# hamtonio.net
KiCad netlist of a schematic drawn in EAGLE
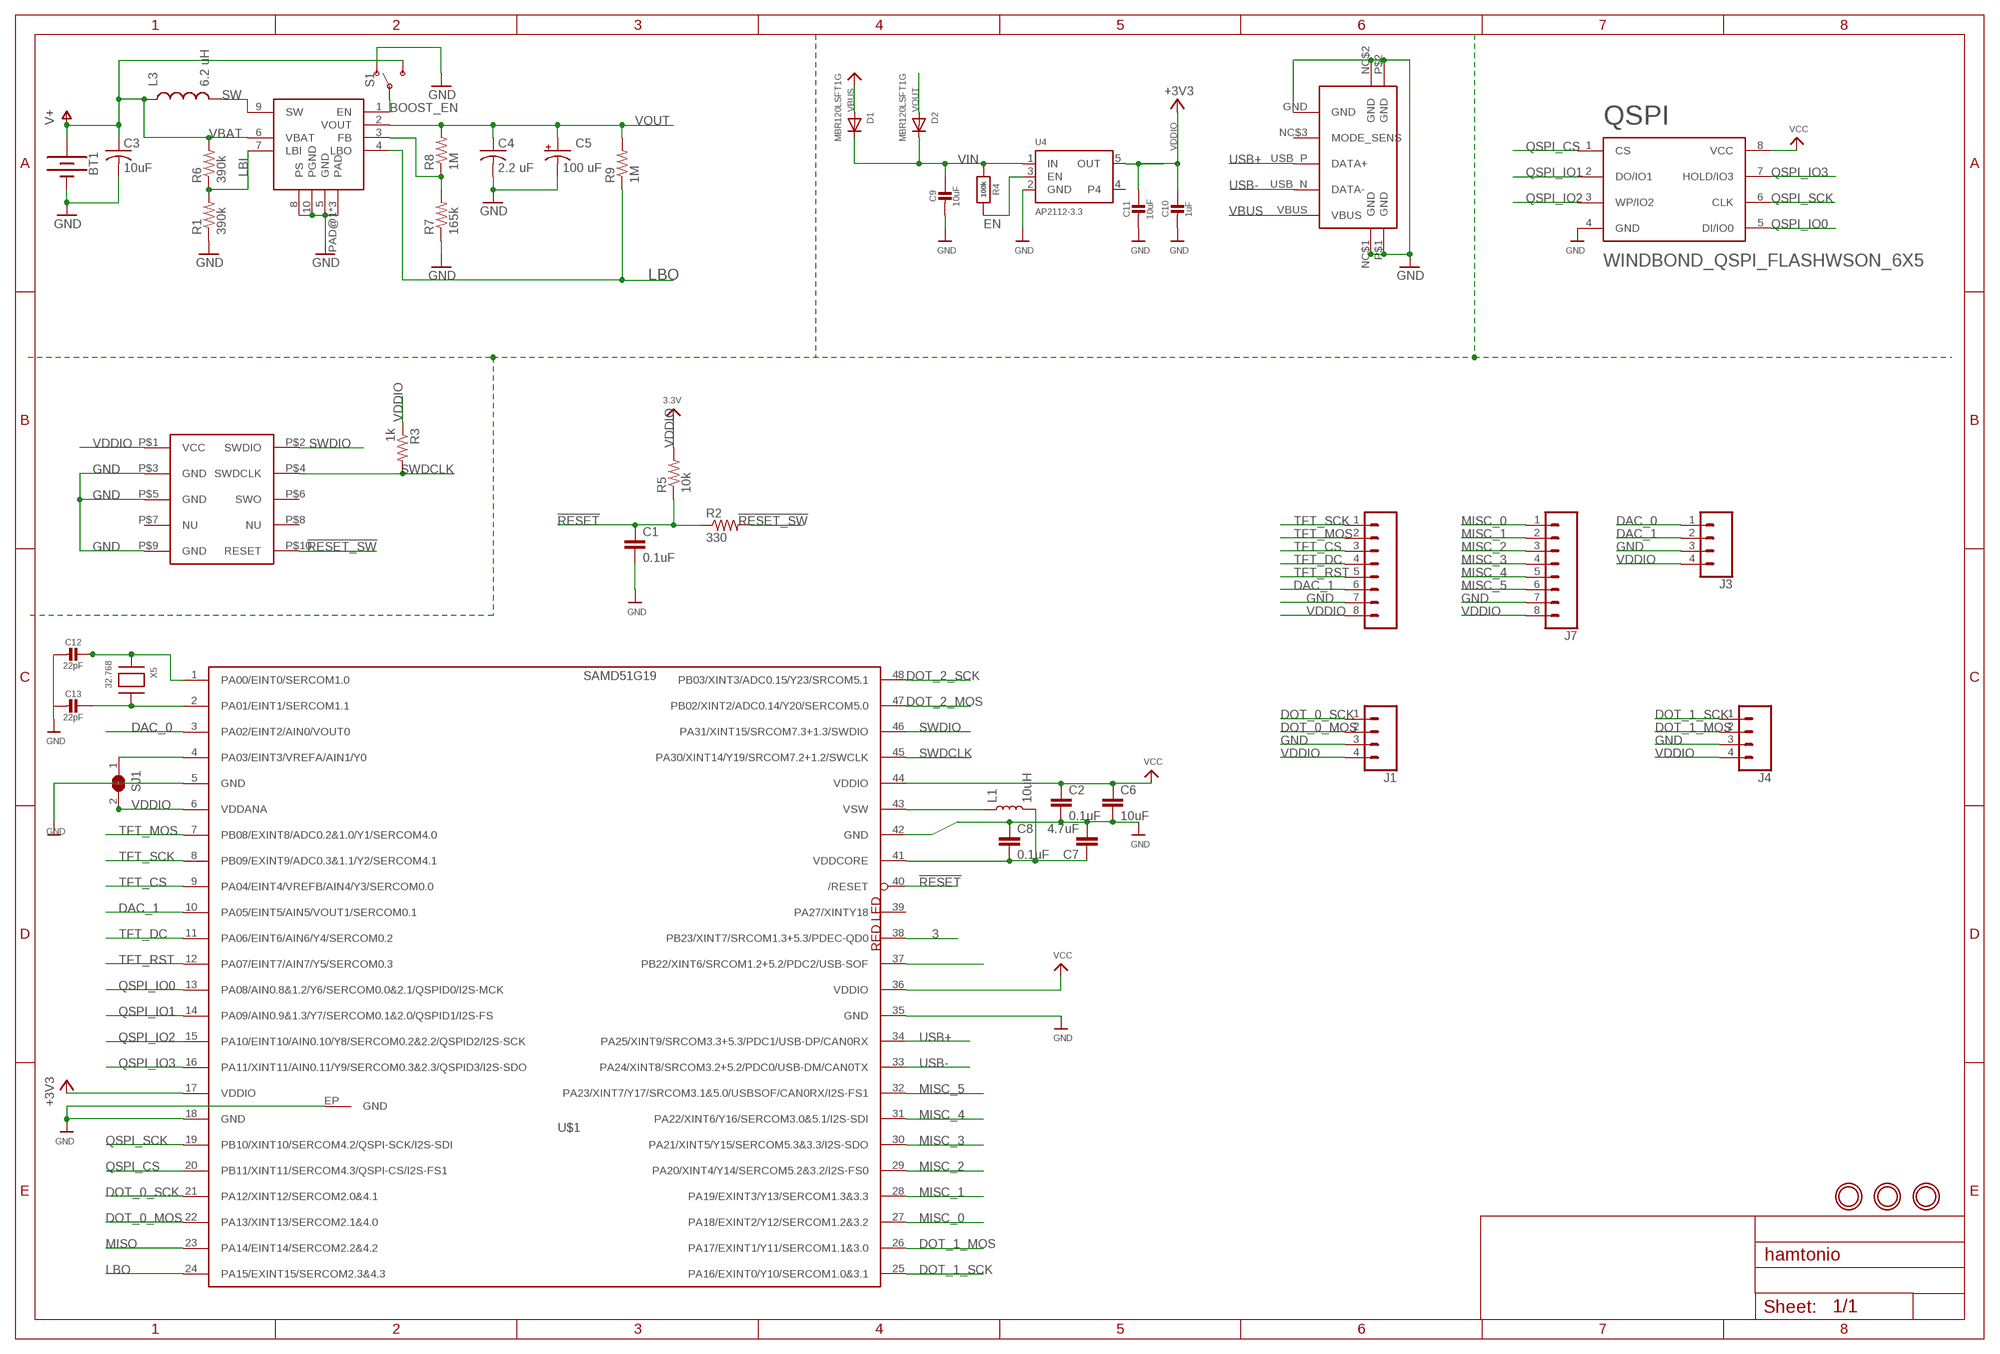
[diagram p0: schematic, sheet 1]

(export (version "E")
  (design (tool "Eeschema 10.0.6"))
  (components
    (comp (ref "BT1")
      (value "BATTERYDUAL_AA_XX")
      (footprint "eagle-import:DUAL_AA")
      (libsource (lib "eagle-import") (part "BATTERYDUAL_AA_XX"))
    )
    (comp (ref "C1")
      (value "0.1uF")
      (footprint "eagle-import:0603")
      (libsource (lib "eagle-import") (part "0.1UF-0603-25V-(+80/-20%)"))
    )
    (comp (ref "C2")
      (value "0.1uF")
      (footprint "eagle-import:0603")
      (libsource (lib "eagle-import") (part "0.1UF-0603-25V-(+80/-20%)"))
    )
    (comp (ref "C3")
      (value "10uF")
      (footprint "eagle-import:C0805K")
      (libsource (lib "eagle-import") (part "C-USC0805K"))
    )
    (comp (ref "C4")
      (value "2.2 uF")
      (footprint "eagle-import:C0805K")
      (libsource (lib "eagle-import") (part "C-USC0805K"))
    )
    (comp (ref "C5")
      (value "100 uF")
      (footprint "eagle-import:CT6032")
      (libsource (lib "eagle-import") (part "CPOL-USCT6032"))
    )
    (comp (ref "C6")
      (value "10uF")
      (footprint "eagle-import:0805")
      (libsource (lib "eagle-import") (part "10UF-0805-10V-10%"))
    )
    (comp (ref "C7")
      (value "4.7uF")
      (footprint "eagle-import:0603")
      (libsource (lib "eagle-import") (part "4.7UF0603"))
    )
    (comp (ref "C8")
      (value "0.1uF")
      (footprint "eagle-import:0603")
      (libsource (lib "eagle-import") (part "0.1UF-0603-25V-(+80/-20%)"))
    )
    (comp (ref "C9")
      (value "10uF")
      (footprint "eagle-import:0805-NO")
      (libsource (lib "eagle-import") (part "CAP_CERAMIC0805-NOOUTLINE"))
    )
    (comp (ref "C10")
      (value "1uF")
      (footprint "eagle-import:0603-NO")
      (libsource (lib "eagle-import") (part "CAP_CERAMIC0603_NO"))
    )
    (comp (ref "C11")
      (value "10uF")
      (footprint "eagle-import:0805-NO")
      (libsource (lib "eagle-import") (part "CAP_CERAMIC0805-NOOUTLINE"))
    )
    (comp (ref "C12")
      (value "22pF")
      (footprint "eagle-import:0603-NO")
      (libsource (lib "eagle-import") (part "CAP_CERAMIC0603_NO"))
    )
    (comp (ref "C13")
      (value "22pF")
      (footprint "eagle-import:0603-NO")
      (libsource (lib "eagle-import") (part "CAP_CERAMIC0603_NO"))
    )
    (comp (ref "D1")
      (value "MBR120LSFT1G")
      (footprint "eagle-import:SOD-123")
      (libsource (lib "eagle-import") (part "DIODESOD-123"))
    )
    (comp (ref "D2")
      (value "MBR120LSFT1G")
      (footprint "eagle-import:SOD-123")
      (libsource (lib "eagle-import") (part "DIODESOD-123"))
    )
    (comp (ref "J1")
      (value "CONN_041X04_NO_SILK")
      (footprint "eagle-import:1X04_NO_SILK")
      (libsource (lib "eagle-import") (part "CONN_041X04_NO_SILK"))
    )
    (comp (ref "J3")
      (value "CONN_041X04_NO_SILK")
      (footprint "eagle-import:1X04_NO_SILK")
      (libsource (lib "eagle-import") (part "CONN_041X04_NO_SILK"))
    )
    (comp (ref "J4")
      (value "CONN_041X04_NO_SILK")
      (footprint "eagle-import:1X04_NO_SILK")
      (libsource (lib "eagle-import") (part "CONN_041X04_NO_SILK"))
    )
    (comp (ref "J6")
      (value "CONN_08NO_SILK_FEMALE_PTH")
      (footprint "eagle-import:1X08_NO_SILK")
      (libsource (lib "eagle-import") (part "CONN_08NO_SILK_FEMALE_PTH"))
    )
    (comp (ref "J7")
      (value "CONN_08NO_SILK_FEMALE_PTH")
      (footprint "eagle-import:1X08_NO_SILK")
      (libsource (lib "eagle-import") (part "CONN_08NO_SILK_FEMALE_PTH"))
    )
    (comp (ref "L1")
      (value "10uH")
      (footprint "eagle-import:1007_INDUCTOR")
      (libsource (lib "eagle-import") (part "1007_INDUCTOR"))
    )
    (comp (ref "L3")
      (value "6.2 uH")
      (footprint "eagle-import:CDRH52D")
      (libsource (lib "eagle-import") (part "INDUCTORSRU1038"))
    )
    (comp (ref "QSPI")
      (value "WINDBOND_QSPI_FLASHWSON_6X5")
      (footprint "eagle-import:WSON_6X5MM")
      (libsource (lib "eagle-import") (part "WINDBOND_QSPI_FLASHWSON_6X5"))
    )
    (comp (ref "R1")
      (value "390k")
      (footprint "eagle-import:R0603")
      (libsource (lib "eagle-import") (part "R-US_R0603"))
    )
    (comp (ref "R2")
      (value "330")
      (footprint "eagle-import:R0603")
      (libsource (lib "eagle-import") (part "R-US_R0603"))
    )
    (comp (ref "R3")
      (value "1k")
      (footprint "eagle-import:R0603")
      (libsource (lib "eagle-import") (part "R-US_R0603"))
    )
    (comp (ref "R4")
      (value "100k")
      (footprint "eagle-import:0603-NO")
      (libsource (lib "eagle-import") (part "RESISTOR_0603_NOOUT"))
    )
    (comp (ref "R5")
      (value "10k")
      (footprint "eagle-import:R0603")
      (libsource (lib "eagle-import") (part "R-US_R0603"))
    )
    (comp (ref "R6")
      (value "390k")
      (footprint "eagle-import:R0603")
      (libsource (lib "eagle-import") (part "R-US_R0603"))
    )
    (comp (ref "R7")
      (value "165k")
      (footprint "eagle-import:R0603")
      (libsource (lib "eagle-import") (part "R-US_R0603"))
    )
    (comp (ref "R8")
      (value "1M")
      (footprint "eagle-import:R0603")
      (libsource (lib "eagle-import") (part "R-US_R0603"))
    )
    (comp (ref "R9")
      (value "1M")
      (footprint "eagle-import:R0603")
      (libsource (lib "eagle-import") (part "R-US_R0603"))
    )
    (comp (ref "S1")
      (value "SWITCH-SPDTSMD_C&K_JS")
      (footprint "eagle-import:SPDT_SMD")
      (libsource (lib "eagle-import") (part "SWITCH-SPDTSMD_C&K_JS"))
    )
    (comp (ref "SJ1")
      (value "SOLDERJUMPERCLOSED")
      (footprint "eagle-import:SOLDERJUMPER_CLOSEDWIRE")
      (libsource (lib "eagle-import") (part "SOLDERJUMPERCLOSED"))
    )
    (comp (ref "U$1")
      (value "SAMD51G19")
      (footprint "eagle-import:QFN-48")
      (libsource (lib "eagle-import") (part "SAMD51G"))
    )
    (comp (ref "U$2")
      (value "SWD_HEADER")
      (footprint "eagle-import:AMPHENOL_SWD")
      (libsource (lib "eagle-import") (part "SWD_HEADER"))
    )
    (comp (ref "U$8")
      (value "TPS61029")
      (footprint "eagle-import:TPS61029")
      (libsource (lib "eagle-import") (part "TPS61029"))
    )
    (comp (ref "U$12")
      (value "AMPHENOL_MICRO_USBAMPHENOL_MICRO_USB_BETTER")
      (footprint "eagle-import:BETTER_AMP_MICRO_USB")
      (libsource (lib "eagle-import") (part "AMPHENOL_MICRO_USBAMPHENOL_MICRO_USB_BETTER"))
    )
    (comp (ref "U$22")
      (value "MOUNTINGHOLE2.5")
      (footprint "eagle-import:MOUNTINGHOLE_2.5_PLATED")
      (libsource (lib "eagle-import") (part "MOUNTINGHOLE2.5"))
    )
    (comp (ref "U$34")
      (value "MOUNTINGHOLE2.5")
      (footprint "eagle-import:MOUNTINGHOLE_2.5_PLATED")
      (libsource (lib "eagle-import") (part "MOUNTINGHOLE2.5"))
    )
    (comp (ref "U$39")
      (value "MOUNTINGHOLE2.5")
      (footprint "eagle-import:MOUNTINGHOLE_2.5_PLATED")
      (libsource (lib "eagle-import") (part "MOUNTINGHOLE2.5"))
    )
    (comp (ref "U4")
      (value "AP2112-3.3")
      (footprint "eagle-import:SOT23-5")
      (libsource (lib "eagle-import") (part "VREG_SOT23-5"))
    )
    (comp (ref "X5")
      (value "32.768")
      (footprint "eagle-import:XTAL3215")
      (libsource (lib "eagle-import") (part "XTAL-3.2X1.5"))
    )
  )
  (nets
    (net (code "1") (name "+3V3") (class "Default")
      (node (ref "C10") (pin "1") (pinfunction "1_1") (pintype "passive"))
      (node (ref "C11") (pin "1") (pinfunction "1_1") (pintype "passive"))
      (node (ref "C2") (pin "1") (pinfunction "1_1") (pintype "passive"))
      (node (ref "C6") (pin "1") (pinfunction "1_1") (pintype "passive"))
      (node (ref "J1") (pin "4") (pinfunction "4_4") (pintype "passive"))
      (node (ref "J3") (pin "4") (pinfunction "4_4") (pintype "passive"))
      (node (ref "J4") (pin "4") (pinfunction "4_4") (pintype "passive"))
      (node (ref "J6") (pin "8") (pinfunction "8_8") (pintype "passive"))
      (node (ref "J7") (pin "8") (pinfunction "8_8") (pintype "passive"))
      (node (ref "QSPI") (pin "8") (pinfunction "VCC_8") (pintype "passive"))
      (node (ref "R3") (pin "1") (pinfunction "1_1") (pintype "passive"))
      (node (ref "R5") (pin "2") (pinfunction "2_2") (pintype "passive"))
      (node (ref "SJ1") (pin "2") (pinfunction "2_2") (pintype "passive"))
      (node (ref "U$1") (pin "17") (pinfunction "VDDIO_17") (pintype "power_in"))
      (node (ref "U$1") (pin "36") (pinfunction "VDDIO_36") (pintype "bidirectional"))
      (node (ref "U$1") (pin "44") (pinfunction "VDDIO_44") (pintype "bidirectional"))
      (node (ref "U$1") (pin "6") (pinfunction "VDDANA_6") (pintype "power_in"))
      (node (ref "U$2") (pin "P$1") (pinfunction "VCC_P$1") (pintype "bidirectional"))
      (node (ref "U4") (pin "5") (pinfunction "OUT_5") (pintype "power_in"))
    )
    (net (code "2") (name "/3") (class "Default")
      (node (ref "U$1") (pin "38") (pinfunction "PB23/XINT7/SRCOM1.3+5.3/PDEC-QD0_38") (pintype "bidirectional"))
    )
    (net (code "3") (name "/BOOST_EN") (class "Default")
      (node (ref "S1") (pin "P$2") (pinfunction "P_P$2") (pintype "passive"))
      (node (ref "S1") (pin "P$5") (pinfunction "P_P$5") (pintype "passive"))
      (node (ref "U$8") (pin "1") (pinfunction "EN_1") (pintype "bidirectional"))
    )
    (net (code "4") (name "/DAC_0") (class "Default")
      (node (ref "J3") (pin "1") (pinfunction "1_1") (pintype "passive"))
      (node (ref "U$1") (pin "3") (pinfunction "PA02/EINT2/AIN0/VOUT0_3") (pintype "bidirectional"))
    )
    (net (code "5") (name "/DAC_1") (class "Default")
      (node (ref "J3") (pin "2") (pinfunction "2_2") (pintype "passive"))
      (node (ref "J6") (pin "6") (pinfunction "6_6") (pintype "passive"))
      (node (ref "U$1") (pin "10") (pinfunction "PA05/EINT5/AIN5/VOUT1/SERCOM0.1_10") (pintype "bidirectional"))
    )
    (net (code "6") (name "/DOT_0_MOS") (class "Default")
      (node (ref "J1") (pin "2") (pinfunction "2_2") (pintype "passive"))
      (node (ref "U$1") (pin "22") (pinfunction "PA13/XINT13/SERCOM2.1&4.0_22") (pintype "bidirectional"))
    )
    (net (code "7") (name "/DOT_0_SCK") (class "Default")
      (node (ref "J1") (pin "1") (pinfunction "1_1") (pintype "passive"))
      (node (ref "U$1") (pin "21") (pinfunction "PA12/XINT12/SERCOM2.0&4.1_21") (pintype "bidirectional"))
    )
    (net (code "8") (name "/DOT_1_MOS") (class "Default")
      (node (ref "J4") (pin "2") (pinfunction "2_2") (pintype "passive"))
      (node (ref "U$1") (pin "26") (pinfunction "PA17/EXINT1/Y11/SERCOM1.1&3.0_26") (pintype "bidirectional"))
    )
    (net (code "9") (name "/DOT_1_SCK") (class "Default")
      (node (ref "J4") (pin "1") (pinfunction "1_1") (pintype "passive"))
      (node (ref "U$1") (pin "25") (pinfunction "PA16/EXINT0/Y10/SERCOM1.0&3.1_25") (pintype "bidirectional"))
    )
    (net (code "10") (name "/DOT_2_MOS") (class "Default")
      (node (ref "U$1") (pin "47") (pinfunction "PB02/XINT2/ADC0.14/Y20/SERCOM5.0_47") (pintype "bidirectional"))
    )
    (net (code "11") (name "/DOT_2_SCK") (class "Default")
      (node (ref "U$1") (pin "48") (pinfunction "PB03/XINT3/ADC0.15/Y23/SRCOM5.1_48") (pintype "bidirectional"))
    )
    (net (code "12") (name "/EN") (class "Default")
      (node (ref "R4") (pin "2") (pinfunction "2_2") (pintype "passive"))
      (node (ref "U4") (pin "3") (pinfunction "EN_3") (pintype "input"))
    )
    (net (code "13") (name "/LBI") (class "Default")
      (node (ref "R1") (pin "2") (pinfunction "2_2") (pintype "passive"))
      (node (ref "R6") (pin "1") (pinfunction "1_1") (pintype "passive"))
      (node (ref "U$8") (pin "7") (pinfunction "LBI_7") (pintype "bidirectional"))
    )
    (net (code "14") (name "/LBO") (class "Default")
      (node (ref "R9") (pin "1") (pinfunction "1_1") (pintype "passive"))
      (node (ref "U$1") (pin "24") (pinfunction "PA15/EXINT15/SERCOM2.3&4.3_24") (pintype "bidirectional"))
      (node (ref "U$8") (pin "4") (pinfunction "LBO_4") (pintype "bidirectional"))
    )
    (net (code "15") (name "/MISC_0") (class "Default")
      (node (ref "J7") (pin "1") (pinfunction "1_1") (pintype "passive"))
      (node (ref "U$1") (pin "27") (pinfunction "PA18/EXINT2/Y12/SERCOM1.2&3.2_27") (pintype "bidirectional"))
    )
    (net (code "16") (name "/MISC_1") (class "Default")
      (node (ref "J7") (pin "2") (pinfunction "2_2") (pintype "passive"))
      (node (ref "U$1") (pin "28") (pinfunction "PA19/EXINT3/Y13/SERCOM1.3&3.3_28") (pintype "bidirectional"))
    )
    (net (code "17") (name "/MISC_2") (class "Default")
      (node (ref "J7") (pin "3") (pinfunction "3_3") (pintype "passive"))
      (node (ref "U$1") (pin "29") (pinfunction "PA20/XINT4/Y14/SERCOM5.2&3.2/I2S-FS0_29") (pintype "bidirectional"))
    )
    (net (code "18") (name "/MISC_3") (class "Default")
      (node (ref "J7") (pin "4") (pinfunction "4_4") (pintype "passive"))
      (node (ref "U$1") (pin "30") (pinfunction "PA21/XINT5/Y15/SERCOM5.3&3.3/I2S-SDO_30") (pintype "bidirectional"))
    )
    (net (code "19") (name "/MISC_4") (class "Default")
      (node (ref "J7") (pin "5") (pinfunction "5_5") (pintype "passive"))
      (node (ref "U$1") (pin "31") (pinfunction "PA22/XINT6/Y16/SERCOM3.0&5.1/I2S-SDI_31") (pintype "bidirectional"))
    )
    (net (code "20") (name "/MISC_5") (class "Default")
      (node (ref "J7") (pin "6") (pinfunction "6_6") (pintype "passive"))
      (node (ref "U$1") (pin "32") (pinfunction "PA23/XINT7/Y17/SRCOM3.1&5.0/USBSOF/CAN0RX/I2S-FS1_32") (pintype "bidirectional"))
    )
    (net (code "21") (name "/MISO") (class "Default")
      (node (ref "U$1") (pin "23") (pinfunction "PA14/EINT14/SERCOM2.2&4.2_23") (pintype "bidirectional"))
    )
    (net (code "22") (name "/QSPI_CS") (class "Default")
      (node (ref "QSPI") (pin "1") (pinfunction "CS_1") (pintype "bidirectional"))
      (node (ref "U$1") (pin "20") (pinfunction "PB11/XINT11/SERCOM4.3/QSPI-CS/I2S-FS1_20") (pintype "bidirectional"))
    )
    (net (code "23") (name "/QSPI_IO0") (class "Default")
      (node (ref "QSPI") (pin "5") (pinfunction "DI/IO0_5") (pintype "bidirectional"))
      (node (ref "U$1") (pin "13") (pinfunction "PA08/AIN0.8&1.2/Y6/SERCOM0.0&2.1/QSPID0/I2S-MCK_13") (pintype "bidirectional"))
    )
    (net (code "24") (name "/QSPI_IO1") (class "Default")
      (node (ref "QSPI") (pin "2") (pinfunction "DO/IO1_2") (pintype "bidirectional"))
      (node (ref "U$1") (pin "14") (pinfunction "PA09/AIN0.9&1.3/Y7/SERCOM0.1&2.0/QSPID1/I2S-FS_14") (pintype "bidirectional"))
    )
    (net (code "25") (name "/QSPI_IO2") (class "Default")
      (node (ref "QSPI") (pin "3") (pinfunction "WP/IO2_3") (pintype "bidirectional"))
      (node (ref "U$1") (pin "15") (pinfunction "PA10/EINT10/AIN0.10/Y8/SERCOM0.2&2.2/QSPID2/I2S-SCK_15") (pintype "bidirectional"))
    )
    (net (code "26") (name "/QSPI_IO3") (class "Default")
      (node (ref "QSPI") (pin "7") (pinfunction "HOLD/IO3_7") (pintype "bidirectional"))
      (node (ref "U$1") (pin "16") (pinfunction "PA11/XINT11/AIN0.11/Y9/SERCOM0.3&2.3/QSPID3/I2S-SDO_16") (pintype "bidirectional"))
    )
    (net (code "27") (name "/QSPI_SCK") (class "Default")
      (node (ref "QSPI") (pin "6") (pinfunction "CLK_6") (pintype "bidirectional"))
      (node (ref "U$1") (pin "19") (pinfunction "PB10/XINT10/SERCOM4.2/QSPI-SCK/I2S-SDI_19") (pintype "bidirectional"))
    )
    (net (code "28") (name "/SW") (class "Default")
      (node (ref "L3") (pin "2") (pinfunction "2_2") (pintype "passive"))
      (node (ref "U$8") (pin "9") (pinfunction "SW_9") (pintype "bidirectional"))
    )
    (net (code "29") (name "/SWDCLK") (class "Default")
      (node (ref "R3") (pin "2") (pinfunction "2_2") (pintype "passive"))
      (node (ref "U$1") (pin "45") (pinfunction "PA30/XINT14/Y19/SRCOM7.2+1.2/SWCLK_45") (pintype "bidirectional"))
      (node (ref "U$2") (pin "P$4") (pinfunction "SWDCLK_P$4") (pintype "bidirectional"))
    )
    (net (code "30") (name "/SWDIO") (class "Default")
      (node (ref "U$1") (pin "46") (pinfunction "PA31/XINT15/SRCOM7.3+1.3/SWDIO_46") (pintype "bidirectional"))
      (node (ref "U$2") (pin "P$2") (pinfunction "SWDIO_P$2") (pintype "bidirectional"))
    )
    (net (code "31") (name "/TFT_CS") (class "Default")
      (node (ref "J6") (pin "3") (pinfunction "3_3") (pintype "passive"))
      (node (ref "U$1") (pin "9") (pinfunction "PA04/EINT4/VREFB/AIN4/Y3/SERCOM0.0_9") (pintype "bidirectional"))
    )
    (net (code "32") (name "/TFT_DC") (class "Default")
      (node (ref "J6") (pin "4") (pinfunction "4_4") (pintype "passive"))
      (node (ref "U$1") (pin "11") (pinfunction "PA06/EINT6/AIN6/Y4/SERCOM0.2_11") (pintype "bidirectional"))
    )
    (net (code "33") (name "/TFT_MOS") (class "Default")
      (node (ref "J6") (pin "2") (pinfunction "2_2") (pintype "passive"))
      (node (ref "U$1") (pin "7") (pinfunction "PB08/EXINT8/ADC0.2&1.0/Y1/SERCOM4.0_7") (pintype "bidirectional"))
    )
    (net (code "34") (name "/TFT_RST") (class "Default")
      (node (ref "J6") (pin "5") (pinfunction "5_5") (pintype "passive"))
      (node (ref "U$1") (pin "12") (pinfunction "PA07/EINT7/AIN7/Y5/SERCOM0.3_12") (pintype "bidirectional"))
    )
    (net (code "35") (name "/TFT_SCK") (class "Default")
      (node (ref "J6") (pin "1") (pinfunction "1_1") (pintype "passive"))
      (node (ref "U$1") (pin "8") (pinfunction "PB09/EXINT9/ADC0.3&1.1/Y2/SERCOM4.1_8") (pintype "bidirectional"))
    )
    (net (code "36") (name "/USB+") (class "Default")
      (node (ref "U$1") (pin "34") (pinfunction "PA25/XINT9/SRCOM3.3+5.3/PDC1/USB-DP/CAN0RX_34") (pintype "bidirectional"))
      (node (ref "U$12") (pin "USB_P") (pinfunction "DATA+_USB_P") (pintype "bidirectional"))
    )
    (net (code "37") (name "/USB-") (class "Default")
      (node (ref "U$1") (pin "33") (pinfunction "PA24/XINT8/SRCOM3.2+5.2/PDC0/USB-DM/CAN0TX_33") (pintype "bidirectional"))
      (node (ref "U$12") (pin "USB_N") (pinfunction "DATA-_USB_N") (pintype "bidirectional"))
    )
    (net (code "38") (name "/VIN") (class "Default")
      (node (ref "C9") (pin "1") (pinfunction "1_1") (pintype "passive"))
      (node (ref "D1") (pin "C") (pinfunction "C_C") (pintype "passive"))
      (node (ref "D2") (pin "C") (pinfunction "C_C") (pintype "passive"))
      (node (ref "R4") (pin "1") (pinfunction "1_1") (pintype "passive"))
      (node (ref "U4") (pin "1") (pinfunction "IN_1") (pintype "power_in"))
    )
    (net (code "39") (name "/VOUT") (class "Default")
      (node (ref "C4") (pin "1") (pinfunction "1_1") (pintype "passive"))
      (node (ref "C5") (pin "+") (pinfunction "+_+") (pintype "passive"))
      (node (ref "D2") (pin "A") (pinfunction "A_A") (pintype "passive"))
      (node (ref "R8") (pin "2") (pinfunction "2_2") (pintype "passive"))
      (node (ref "R9") (pin "2") (pinfunction "2_2") (pintype "passive"))
      (node (ref "U$8") (pin "2") (pinfunction "VOUT_2") (pintype "bidirectional"))
    )
    (net (code "40") (name "/~{RESET_SW}") (class "Default")
      (node (ref "R2") (pin "2") (pinfunction "2_2") (pintype "passive"))
      (node (ref "U$2") (pin "P$10") (pinfunction "RESET_P$10") (pintype "bidirectional"))
    )
    (net (code "41") (name "/~{RESET}") (class "Default")
      (node (ref "C1") (pin "1") (pinfunction "1_1") (pintype "passive"))
      (node (ref "R2") (pin "1") (pinfunction "1_1") (pintype "passive"))
      (node (ref "R5") (pin "1") (pinfunction "1_1") (pintype "passive"))
      (node (ref "U$1") (pin "40") (pinfunction "/RESET_40") (pintype "bidirectional"))
    )
    (net (code "42") (name "GND") (class "Default")
      (node (ref "BT1") (pin "V-") (pinfunction "-_V-") (pintype "power_in"))
      (node (ref "C1") (pin "2") (pinfunction "2_2") (pintype "passive"))
      (node (ref "C10") (pin "2") (pinfunction "2_2") (pintype "passive"))
      (node (ref "C11") (pin "2") (pinfunction "2_2") (pintype "passive"))
      (node (ref "C12") (pin "2") (pinfunction "2_2") (pintype "passive"))
      (node (ref "C13") (pin "2") (pinfunction "2_2") (pintype "passive"))
      (node (ref "C2") (pin "2") (pinfunction "2_2") (pintype "passive"))
      (node (ref "C3") (pin "2") (pinfunction "2_2") (pintype "passive"))
      (node (ref "C4") (pin "2") (pinfunction "2_2") (pintype "passive"))
      (node (ref "C5") (pin "-") (pinfunction "-_-") (pintype "passive"))
      (node (ref "C6") (pin "2") (pinfunction "2_2") (pintype "passive"))
      (node (ref "C7") (pin "2") (pinfunction "2_2") (pintype "passive"))
      (node (ref "C8") (pin "1") (pinfunction "1_1") (pintype "passive"))
      (node (ref "C9") (pin "2") (pinfunction "2_2") (pintype "passive"))
      (node (ref "J1") (pin "3") (pinfunction "3_3") (pintype "passive"))
      (node (ref "J3") (pin "3") (pinfunction "3_3") (pintype "passive"))
      (node (ref "J4") (pin "3") (pinfunction "3_3") (pintype "passive"))
      (node (ref "J6") (pin "7") (pinfunction "7_7") (pintype "passive"))
      (node (ref "J7") (pin "7") (pinfunction "7_7") (pintype "passive"))
      (node (ref "QSPI") (pin "4") (pinfunction "GND_4") (pintype "power_in"))
      (node (ref "R1") (pin "1") (pinfunction "1_1") (pintype "passive"))
      (node (ref "R7") (pin "1") (pinfunction "1_1") (pintype "passive"))
      (node (ref "S1") (pin "P$1") (pinfunction "O_P$1") (pintype "passive"))
      (node (ref "S1") (pin "P$6") (pinfunction "O_P$6") (pintype "passive"))
      (node (ref "U$1") (pin "18") (pinfunction "GND_18") (pintype "power_in"))
      (node (ref "U$1") (pin "35") (pinfunction "GND_35") (pintype "power_in"))
      (node (ref "U$1") (pin "42") (pinfunction "GND_42") (pintype "power_in"))
      (node (ref "U$1") (pin "5") (pinfunction "GND_5") (pintype "power_in"))
      (node (ref "U$1") (pin "EP") (pinfunction "GND_EP") (pintype "power_in"))
      (node (ref "U$12") (pin "GND") (pinfunction "GND_GND") (pintype "bidirectional"))
      (node (ref "U$12") (pin "NC$1") (pinfunction "GND_NC$1") (pintype "bidirectional"))
      (node (ref "U$12") (pin "NC$2") (pinfunction "GND_NC$2") (pintype "bidirectional"))
      (node (ref "U$12") (pin "P$1") (pinfunction "GND_P$1") (pintype "bidirectional"))
      (node (ref "U$12") (pin "P$2") (pinfunction "GND_P$2") (pintype "bidirectional"))
      (node (ref "U$2") (pin "P$3") (pinfunction "GND_P$3") (pintype "bidirectional"))
      (node (ref "U$2") (pin "P$5") (pinfunction "GND_P$5") (pintype "bidirectional"))
      (node (ref "U$2") (pin "P$9") (pinfunction "GND_P$9") (pintype "bidirectional"))
      (node (ref "U$8") (pin "10") (pinfunction "PGND_10") (pintype "bidirectional"))
      (node (ref "U$8") (pin "5") (pinfunction "GND_5") (pintype "bidirectional"))
      (node (ref "U$8") (pin "8") (pinfunction "PS_8") (pintype "bidirectional"))
      (node (ref "U$8") (pin "PAD@1") (pinfunction "PAD_PAD@1") (pintype "bidirectional"))
      (node (ref "U$8") (pin "PAD@2") (pinfunction "PAD_PAD@2") (pintype "bidirectional"))
      (node (ref "U$8") (pin "PAD@3") (pinfunction "PAD_PAD@3") (pintype "bidirectional"))
      (node (ref "U4") (pin "2") (pinfunction "GND_2") (pintype "power_in"))
    )
    (net (code "43") (name "Net-(L1-1)") (class "Default")
      (node (ref "L1") (pin "P$1") (pinfunction "1_P$1") (pintype "passive"))
      (node (ref "U$1") (pin "43") (pinfunction "VSW_43") (pintype "bidirectional"))
    )
    (net (code "44") (name "Net-(L1-2)") (class "Default")
      (node (ref "C7") (pin "1") (pinfunction "1_1") (pintype "passive"))
      (node (ref "C8") (pin "2") (pinfunction "2_2") (pintype "passive"))
      (node (ref "L1") (pin "P$2") (pinfunction "2_P$2") (pintype "passive"))
      (node (ref "U$1") (pin "41") (pinfunction "VDDCORE_41") (pintype "power_in"))
    )
    (net (code "45") (name "Net-(U$1-PA00{slash}EINT0{slash}SERCOM1.0)") (class "Default")
      (node (ref "C12") (pin "1") (pinfunction "1_1") (pintype "passive"))
      (node (ref "U$1") (pin "1") (pinfunction "PA00/EINT0/SERCOM1.0_1") (pintype "bidirectional"))
      (node (ref "X5") (pin "P$1") (pinfunction "P$1_P$1") (pintype "bidirectional"))
    )
    (net (code "46") (name "Net-(U$1-PA01{slash}EINT1{slash}SERCOM1.1)") (class "Default")
      (node (ref "C13") (pin "1") (pinfunction "1_1") (pintype "passive"))
      (node (ref "U$1") (pin "2") (pinfunction "PA01/EINT1/SERCOM1.1_2") (pintype "bidirectional"))
      (node (ref "X5") (pin "P$2") (pinfunction "P$2_P$2") (pintype "bidirectional"))
    )
    (net (code "47") (name "Net-(U$1-PA03{slash}EINT3{slash}VREFA{slash}AIN1{slash}Y0)") (class "Default")
      (node (ref "SJ1") (pin "1") (pinfunction "1_1") (pintype "passive"))
      (node (ref "U$1") (pin "4") (pinfunction "PA03/EINT3/VREFA/AIN1/Y0_4") (pintype "bidirectional"))
    )
    (net (code "48") (name "Net-(U$8-FB)") (class "Default")
      (node (ref "R7") (pin "2") (pinfunction "2_2") (pintype "passive"))
      (node (ref "R8") (pin "1") (pinfunction "1_1") (pintype "passive"))
      (node (ref "U$8") (pin "3") (pinfunction "FB_3") (pintype "bidirectional"))
    )
    (net (code "49") (name "V+") (class "Default")
      (node (ref "BT1") (pin "V+") (pinfunction "+_V+") (pintype "power_in"))
      (node (ref "C3") (pin "1") (pinfunction "1_1") (pintype "passive"))
      (node (ref "L3") (pin "1") (pinfunction "1_1") (pintype "passive"))
      (node (ref "R6") (pin "2") (pinfunction "2_2") (pintype "passive"))
      (node (ref "S1") (pin "P$3") (pinfunction "S_P$3") (pintype "passive"))
      (node (ref "S1") (pin "P$4") (pinfunction "S_P$4") (pintype "passive"))
      (node (ref "U$8") (pin "6") (pinfunction "VBAT_6") (pintype "bidirectional"))
    )
    (net (code "50") (name "VBUS") (class "Default")
      (node (ref "D1") (pin "A") (pinfunction "A_A") (pintype "passive"))
      (node (ref "U$12") (pin "VBUS") (pinfunction "VBUS_VBUS") (pintype "bidirectional"))
    )
    (net (code "51") (name "unconnected-(U$1-PA27{slash}XINTY18-Pad39)") (class "Default")
      (node (ref "U$1") (pin "39") (pinfunction "PA27/XINTY18_39") (pintype "bidirectional"))
    )
    (net (code "52") (name "unconnected-(U$1-PB22{slash}XINT6{slash}SRCOM1.2+5.2{slash}PDC2{slash}USB-SOF-Pad37)") (class "Default")
      (node (ref "U$1") (pin "37") (pinfunction "PB22/XINT6/SRCOM1.2+5.2/PDC2/USB-SOF_37") (pintype "bidirectional"))
    )
    (net (code "53") (name "unconnected-(U$2-NU-PadP$7)") (class "Default")
      (node (ref "U$2") (pin "P$7") (pinfunction "NU_P$7") (pintype "bidirectional"))
    )
    (net (code "54") (name "unconnected-(U$2-NU-PadP$8)") (class "Default")
      (node (ref "U$2") (pin "P$8") (pinfunction "NU_P$8") (pintype "bidirectional"))
    )
    (net (code "55") (name "unconnected-(U$2-SWO-PadP$6)") (class "Default")
      (node (ref "U$2") (pin "P$6") (pinfunction "SWO_P$6") (pintype "bidirectional"))
    )
    (net (code "56") (name "unconnected-(U$12-MODE_SENS-PadNC$3)") (class "Default")
      (node (ref "U$12") (pin "NC$3") (pinfunction "MODE_SENS_NC$3") (pintype "bidirectional"))
    )
    (net (code "57") (name "unconnected-(U4-P4-Pad4)") (class "Default")
      (node (ref "U4") (pin "4") (pinfunction "P4_4") (pintype "bidirectional"))
    )
  )
)
